# Blinkenlights.net
KiCad netlist of a schematic drawn in EAGLE
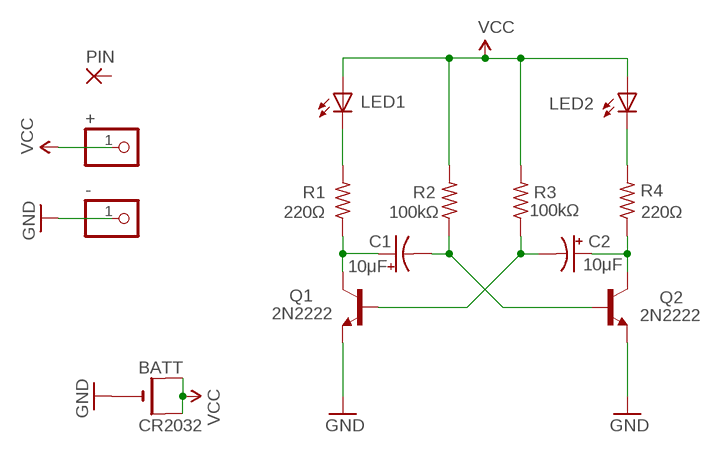
[diagram p0: schematic, sheet 1]

(export (version "E")
  (design (tool "Eeschema 10.0.6"))
  (components
    (comp (ref "+")
      (value "PINHD-1X1CB")
      (footprint "eagle-import:1X01-CLEANBIG")
      (libsource (lib "eagle-import") (part "PINHD-1X1CB"))
    )
    (comp (ref "-")
      (value "PINHD-1X1CB")
      (footprint "eagle-import:1X01-CLEANBIG")
      (libsource (lib "eagle-import") (part "PINHD-1X1CB"))
    )
    (comp (ref "BATT")
      (value "CR2032")
      (footprint "eagle-import:CR2032-SMD")
      (libsource (lib "eagle-import") (part "CR2032SMT"))
    )
    (comp (ref "C1")
      (value "10μF")
      (footprint "eagle-import:E-2.54-05")
      (libsource (lib "eagle-import") (part "CAP-POL_E-2.54-05"))
    )
    (comp (ref "C2")
      (value "10μF")
      (footprint "eagle-import:E-2.54-05")
      (libsource (lib "eagle-import") (part "CAP-POL_E-2.54-05"))
    )
    (comp (ref "LED1")
      (value "LED5MM_BIG")
      (footprint "eagle-import:LED5MM_BIG")
      (libsource (lib "eagle-import") (part "LED5MM_BIG"))
    )
    (comp (ref "LED2")
      (value "LED5MM_BIG")
      (footprint "eagle-import:LED5MM_BIG")
      (libsource (lib "eagle-import") (part "LED5MM_BIG"))
    )
    (comp (ref "PIN")
      (value "3,17/1,3")
      (footprint "eagle-import:3,17_1,3")
      (libsource (lib "eagle-import") (part "3,17/1,3"))
    )
    (comp (ref "Q1")
      (value "2N2222")
      (footprint "eagle-import:TO92-EBC-OVAL")
      (libsource (lib "eagle-import") (part "2N2222"))
    )
    (comp (ref "Q2")
      (value "2N2222")
      (footprint "eagle-import:TO92-EBC-OVAL")
      (libsource (lib "eagle-import") (part "2N2222"))
    )
    (comp (ref "R1")
      (value "220Ω")
      (footprint "eagle-import:0207_10_BIG")
      (libsource (lib "eagle-import") (part "RESISTOR-0207/10_BIG"))
    )
    (comp (ref "R2")
      (value "100kΩ")
      (footprint "eagle-import:0207_10_BIG")
      (libsource (lib "eagle-import") (part "RESISTOR-0207/10_BIG"))
    )
    (comp (ref "R3")
      (value "100kΩ")
      (footprint "eagle-import:0207_10_BIG")
      (libsource (lib "eagle-import") (part "RESISTOR-0207/10_BIG"))
    )
    (comp (ref "R4")
      (value "220Ω")
      (footprint "eagle-import:0207_10_BIG")
      (libsource (lib "eagle-import") (part "RESISTOR-0207/10_BIG"))
    )
  )
  (nets
    (net (code "1") (name "GND") (class "Default")
      (node (ref "-") (pin "1") (pinfunction "1_1") (pintype "passive"))
      (node (ref "BATT") (pin "-") (pinfunction "-_-") (pintype "passive"))
      (node (ref "Q1") (pin "E") (pinfunction "E_E") (pintype "passive"))
      (node (ref "Q2") (pin "E") (pinfunction "E_E") (pintype "passive"))
    )
    (net (code "2") (name "Net-(C1-Pad+)") (class "Default")
      (node (ref "C1") (pin "+") (pinfunction "+_+") (pintype "passive"))
      (node (ref "Q1") (pin "C") (pinfunction "C_C") (pintype "passive"))
      (node (ref "R1") (pin "1") (pinfunction "1_1") (pintype "passive"))
    )
    (net (code "3") (name "Net-(C1-Pad-)") (class "Default")
      (node (ref "C1") (pin "-") (pinfunction "-_-") (pintype "passive"))
      (node (ref "Q2") (pin "B") (pinfunction "B_B") (pintype "passive"))
      (node (ref "R2") (pin "1") (pinfunction "1_1") (pintype "passive"))
    )
    (net (code "4") (name "Net-(C2-Pad+)") (class "Default")
      (node (ref "C2") (pin "+") (pinfunction "+_+") (pintype "passive"))
      (node (ref "Q2") (pin "C") (pinfunction "C_C") (pintype "passive"))
      (node (ref "R4") (pin "1") (pinfunction "1_1") (pintype "passive"))
    )
    (net (code "5") (name "Net-(C2-Pad-)") (class "Default")
      (node (ref "C2") (pin "-") (pinfunction "-_-") (pintype "passive"))
      (node (ref "Q1") (pin "B") (pinfunction "B_B") (pintype "passive"))
      (node (ref "R3") (pin "1") (pinfunction "1_1") (pintype "passive"))
    )
    (net (code "6") (name "Net-(LED1-C)") (class "Default")
      (node (ref "LED1") (pin "K") (pinfunction "C_K") (pintype "passive"))
      (node (ref "R1") (pin "2") (pinfunction "2_2") (pintype "passive"))
    )
    (net (code "7") (name "Net-(LED2-C)") (class "Default")
      (node (ref "LED2") (pin "K") (pinfunction "C_K") (pintype "passive"))
      (node (ref "R4") (pin "2") (pinfunction "2_2") (pintype "passive"))
    )
    (net (code "8") (name "VCC") (class "Default")
      (node (ref "+") (pin "1") (pinfunction "1_1") (pintype "passive"))
      (node (ref "BATT") (pin "+$1") (pinfunction "+_+$1") (pintype "passive"))
      (node (ref "BATT") (pin "+$2") (pinfunction "+1_+$2") (pintype "passive"))
      (node (ref "LED1") (pin "A") (pinfunction "A_A") (pintype "passive"))
      (node (ref "LED2") (pin "A") (pinfunction "A_A") (pintype "passive"))
      (node (ref "R2") (pin "2") (pinfunction "2_2") (pintype "passive"))
      (node (ref "R3") (pin "2") (pinfunction "2_2") (pintype "passive"))
    )
    (net (code "9") (name "unconnected-(PIN-P-Pad1)") (class "Default")
      (node (ref "PIN") (pin "1") (pinfunction "P_1") (pintype "passive"))
    )
  )
)
